# mdac-attenuator.net
KiCad netlist of a schematic drawn in EAGLE
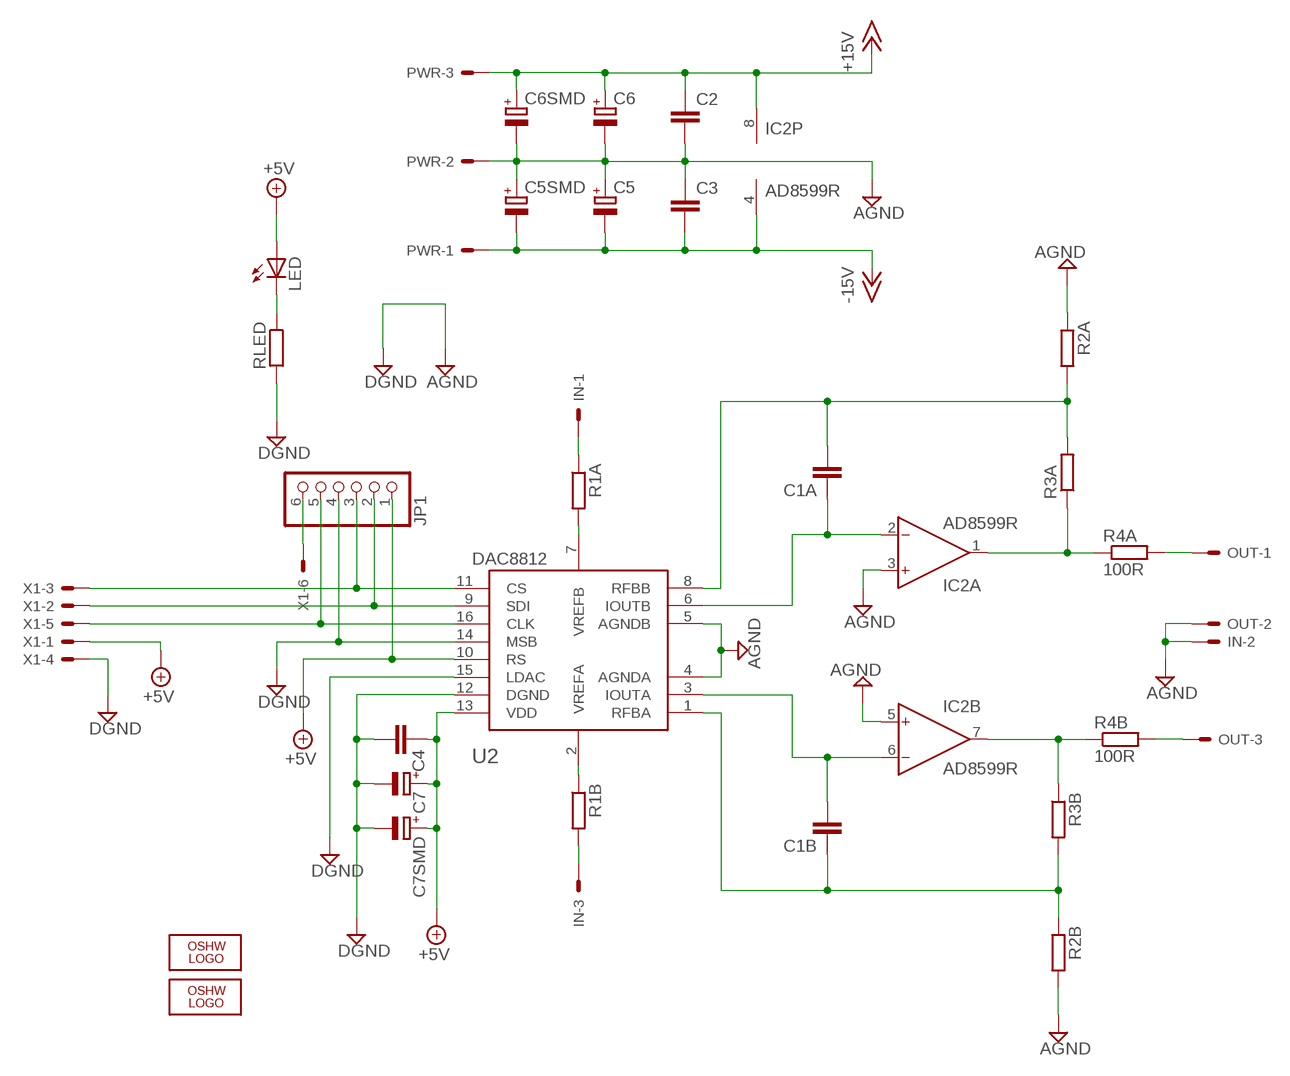
[diagram p0: schematic, sheet 1]

(export (version "E")
  (design (tool "Eeschema 10.0.6"))
  (components
    (comp (ref "C1A")
      (value "C-EUC0805")
      (footprint "eagle-import:C0805")
      (libsource (lib "eagle-import") (part "C-EUC0805"))
    )
    (comp (ref "C1B")
      (value "C-EUC0805")
      (footprint "eagle-import:C0805")
      (libsource (lib "eagle-import") (part "C-EUC0805"))
    )
    (comp (ref "C2")
      (value "C-EUC1206")
      (footprint "eagle-import:C1206")
      (libsource (lib "eagle-import") (part "C-EUC1206"))
    )
    (comp (ref "C3")
      (value "C-EUC1206")
      (footprint "eagle-import:C1206")
      (libsource (lib "eagle-import") (part "C-EUC1206"))
    )
    (comp (ref "C4")
      (value "C-EUC1206")
      (footprint "eagle-import:C1206")
      (libsource (lib "eagle-import") (part "C-EUC1206"))
    )
    (comp (ref "C5")
      (value "CPOL-EUE3.5-8")
      (footprint "eagle-import:E3,5-8")
      (libsource (lib "eagle-import") (part "CPOL-EUE3.5-8"))
    )
    (comp (ref "C5SMD")
      (value "CPOL-EUE")
      (footprint "eagle-import:PANASONIC_E")
      (libsource (lib "eagle-import") (part "CPOL-EUE"))
    )
    (comp (ref "C6")
      (value "CPOL-EUE3.5-8")
      (footprint "eagle-import:E3,5-8")
      (libsource (lib "eagle-import") (part "CPOL-EUE3.5-8"))
    )
    (comp (ref "C6SMD")
      (value "CPOL-EUE")
      (footprint "eagle-import:PANASONIC_E")
      (libsource (lib "eagle-import") (part "CPOL-EUE"))
    )
    (comp (ref "C7")
      (value "CPOL-EUE3.5-8")
      (footprint "eagle-import:E3,5-8")
      (libsource (lib "eagle-import") (part "CPOL-EUE3.5-8"))
    )
    (comp (ref "C7SMD")
      (value "CPOL-EUD")
      (footprint "eagle-import:PANASONIC_D")
      (libsource (lib "eagle-import") (part "CPOL-EUD"))
    )
    (comp (ref "IC2")
      (value "AD8599R")
      (footprint "eagle-import:SO8")
      (libsource (lib "eagle-import") (part "AD8599R"))
    )
    (comp (ref "IN")
      (value "22-23-2031")
      (footprint "eagle-import:22-23-2031")
      (fields (field (name "MF") "MOLEX"))
      (libsource (lib "eagle-import") (part "22-23-2031"))
    )
    (comp (ref "JP1")
      (value "PINHD-1X6")
      (footprint "eagle-import:1X06")
      (libsource (lib "eagle-import") (part "PINHD-1X6"))
    )
    (comp (ref "LED")
      (value "LEDSMT1206")
      (footprint "eagle-import:1206")
      (libsource (lib "eagle-import") (part "LEDSMT1206"))
    )
    (comp (ref "LOGO1")
      (value "OSHW_LOGO_FILLX0200-NT")
      (footprint "eagle-import:OSHW_FILLX200_NOTEXT")
      (libsource (lib "eagle-import") (part "OSHW_LOGO_FILLX0200-NT"))
    )
    (comp (ref "LOGO2")
      (value "OSHW_LOGO_FILLX0200-NT")
      (footprint "eagle-import:OSHW_FILLX200_NOTEXT")
      (libsource (lib "eagle-import") (part "OSHW_LOGO_FILLX0200-NT"))
    )
    (comp (ref "OUT")
      (value "22-23-2031")
      (footprint "eagle-import:22-23-2031")
      (fields (field (name "MF") "MOLEX"))
      (libsource (lib "eagle-import") (part "22-23-2031"))
    )
    (comp (ref "PWR")
      (value "22-23-2031")
      (footprint "eagle-import:22-23-2031")
      (fields (field (name "MF") "MOLEX"))
      (libsource (lib "eagle-import") (part "22-23-2031"))
    )
    (comp (ref "R1A")
      (value "R-EU_R1206")
      (footprint "eagle-import:R1206")
      (libsource (lib "eagle-import") (part "R-EU_R1206"))
    )
    (comp (ref "R1B")
      (value "R-EU_R1206")
      (footprint "eagle-import:R1206")
      (libsource (lib "eagle-import") (part "R-EU_R1206"))
    )
    (comp (ref "R2A")
      (value "R-EU_R1206")
      (footprint "eagle-import:R1206")
      (libsource (lib "eagle-import") (part "R-EU_R1206"))
    )
    (comp (ref "R2B")
      (value "R-EU_R1206")
      (footprint "eagle-import:R1206")
      (libsource (lib "eagle-import") (part "R-EU_R1206"))
    )
    (comp (ref "R3A")
      (value "R-EU_R1206")
      (footprint "eagle-import:R1206")
      (libsource (lib "eagle-import") (part "R-EU_R1206"))
    )
    (comp (ref "R3B")
      (value "R-EU_R1206")
      (footprint "eagle-import:R1206")
      (libsource (lib "eagle-import") (part "R-EU_R1206"))
    )
    (comp (ref "R4A")
      (value "100R")
      (footprint "eagle-import:R1206")
      (libsource (lib "eagle-import") (part "R-EU_R1206"))
    )
    (comp (ref "R4B")
      (value "100R")
      (footprint "eagle-import:R1206")
      (libsource (lib "eagle-import") (part "R-EU_R1206"))
    )
    (comp (ref "RLED")
      (value "R-EU_R1206")
      (footprint "eagle-import:R1206")
      (libsource (lib "eagle-import") (part "R-EU_R1206"))
    )
    (comp (ref "U2")
      (value "DAC8812")
      (footprint "eagle-import:TSSOP16")
      (libsource (lib "eagle-import") (part "DAC8812"))
    )
    (comp (ref "X1")
      (value "22-23-2061")
      (footprint "eagle-import:22-23-2061")
      (fields (field (name "MF") "MOLEX"))
      (libsource (lib "eagle-import") (part "22-23-2061"))
    )
  )
  (nets
    (net (code "1") (name "+5V") (class "Default")
      (node (ref "C4") (pin "1") (pinfunction "1_1") (pintype "passive"))
      (node (ref "C7") (pin "+") (pinfunction "+_+") (pintype "passive"))
      (node (ref "C7SMD") (pin "+") (pinfunction "+_+") (pintype "passive"))
      (node (ref "JP1") (pin "1") (pinfunction "1_1") (pintype "passive"))
      (node (ref "LED") (pin "A") (pinfunction "A_A") (pintype "passive"))
      (node (ref "U2") (pin "10") (pinfunction "RS_10") (pintype "input"))
      (node (ref "U2") (pin "13") (pinfunction "VDD_13") (pintype "power_in"))
      (node (ref "X1") (pin "1") (pinfunction "S_1") (pintype "passive"))
    )
    (net (code "2") (name "+15V") (class "Default")
      (node (ref "C2") (pin "1") (pinfunction "1_1") (pintype "passive"))
      (node (ref "C6") (pin "+") (pinfunction "+_+") (pintype "passive"))
      (node (ref "C6SMD") (pin "+") (pinfunction "+_+") (pintype "passive"))
      (node (ref "IC2") (pin "8") (pinfunction "V+_8") (pintype "power_in"))
      (node (ref "PWR") (pin "3") (pinfunction "S_3") (pintype "passive"))
    )
    (net (code "3") (name "-15V") (class "Default")
      (node (ref "C3") (pin "2") (pinfunction "2_2") (pintype "passive"))
      (node (ref "C5") (pin "-") (pinfunction "-_-") (pintype "passive"))
      (node (ref "C5SMD") (pin "-") (pinfunction "-_-") (pintype "passive"))
      (node (ref "IC2") (pin "4") (pinfunction "V-_4") (pintype "power_in"))
      (node (ref "PWR") (pin "1") (pinfunction "S_1") (pintype "passive"))
    )
    (net (code "4") (name "AGND") (class "Default")
      (node (ref "C2") (pin "2") (pinfunction "2_2") (pintype "passive"))
      (node (ref "C3") (pin "1") (pinfunction "1_1") (pintype "passive"))
      (node (ref "C4") (pin "2") (pinfunction "2_2") (pintype "passive"))
      (node (ref "C5") (pin "+") (pinfunction "+_+") (pintype "passive"))
      (node (ref "C5SMD") (pin "+") (pinfunction "+_+") (pintype "passive"))
      (node (ref "C6") (pin "-") (pinfunction "-_-") (pintype "passive"))
      (node (ref "C6SMD") (pin "-") (pinfunction "-_-") (pintype "passive"))
      (node (ref "C7") (pin "-") (pinfunction "-_-") (pintype "passive"))
      (node (ref "C7SMD") (pin "-") (pinfunction "-_-") (pintype "passive"))
      (node (ref "IC2") (pin "3") (pinfunction "IN+_3") (pintype "input"))
      (node (ref "IC2") (pin "5") (pinfunction "IN+_5") (pintype "input"))
      (node (ref "IN") (pin "2") (pinfunction "S_2") (pintype "passive"))
      (node (ref "JP1") (pin "4") (pinfunction "4_4") (pintype "passive"))
      (node (ref "OUT") (pin "2") (pinfunction "S_2") (pintype "passive"))
      (node (ref "PWR") (pin "2") (pinfunction "S_2") (pintype "passive"))
      (node (ref "R2A") (pin "1") (pinfunction "1_1") (pintype "passive"))
      (node (ref "R2B") (pin "2") (pinfunction "2_2") (pintype "passive"))
      (node (ref "RLED") (pin "2") (pinfunction "2_2") (pintype "passive"))
      (node (ref "U2") (pin "12") (pinfunction "DGND_12") (pintype "power_in"))
      (node (ref "U2") (pin "14") (pinfunction "MSB_14") (pintype "input"))
      (node (ref "U2") (pin "15") (pinfunction "LDAC_15") (pintype "input"))
      (node (ref "U2") (pin "4") (pinfunction "AGNDA_4") (pintype "output"))
      (node (ref "U2") (pin "5") (pinfunction "AGNDB_5") (pintype "output"))
      (node (ref "X1") (pin "4") (pinfunction "S_4") (pintype "passive"))
    )
    (net (code "5") (name "Net-(IC2A-IN-)") (class "Default")
      (node (ref "C1A") (pin "1") (pinfunction "1_1") (pintype "passive"))
      (node (ref "IC2") (pin "2") (pinfunction "IN-_2") (pintype "input"))
      (node (ref "U2") (pin "6") (pinfunction "IOUTB_6") (pintype "output"))
    )
    (net (code "6") (name "Net-(IC2A-OUT)") (class "Default")
      (node (ref "IC2") (pin "1") (pinfunction "OUT_1") (pintype "output"))
      (node (ref "R3A") (pin "1") (pinfunction "1_1") (pintype "passive"))
      (node (ref "R4A") (pin "1") (pinfunction "1_1") (pintype "passive"))
    )
    (net (code "7") (name "Net-(IC2B-IN-)") (class "Default")
      (node (ref "C1B") (pin "2") (pinfunction "2_2") (pintype "passive"))
      (node (ref "IC2") (pin "6") (pinfunction "IN-_6") (pintype "input"))
      (node (ref "U2") (pin "3") (pinfunction "IOUTA_3") (pintype "output"))
    )
    (net (code "8") (name "Net-(IC2B-OUT)") (class "Default")
      (node (ref "IC2") (pin "7") (pinfunction "OUT_7") (pintype "output"))
      (node (ref "R3B") (pin "1") (pinfunction "1_1") (pintype "passive"))
      (node (ref "R4B") (pin "1") (pinfunction "1_1") (pintype "passive"))
    )
    (net (code "9") (name "Net-(INA-S)") (class "Default")
      (node (ref "IN") (pin "1") (pinfunction "S_1") (pintype "passive"))
      (node (ref "R1A") (pin "1") (pinfunction "1_1") (pintype "passive"))
    )
    (net (code "10") (name "Net-(INC-S)") (class "Default")
      (node (ref "IN") (pin "3") (pinfunction "S_3") (pintype "passive"))
      (node (ref "R1B") (pin "2") (pinfunction "2_2") (pintype "passive"))
    )
    (net (code "11") (name "Net-(LED-PadC)") (class "Default")
      (node (ref "LED") (pin "C") (pinfunction "C_C") (pintype "passive"))
      (node (ref "RLED") (pin "1") (pinfunction "1_1") (pintype "passive"))
    )
    (net (code "12") (name "Net-(OUTA-S)") (class "Default")
      (node (ref "OUT") (pin "1") (pinfunction "S_1") (pintype "passive"))
      (node (ref "R4A") (pin "2") (pinfunction "2_2") (pintype "passive"))
    )
    (net (code "13") (name "Net-(OUTC-S)") (class "Default")
      (node (ref "OUT") (pin "3") (pinfunction "S_3") (pintype "passive"))
      (node (ref "R4B") (pin "2") (pinfunction "2_2") (pintype "passive"))
    )
    (net (code "14") (name "Net-(U2-CLK)") (class "Default")
      (node (ref "JP1") (pin "5") (pinfunction "5_5") (pintype "passive"))
      (node (ref "U2") (pin "16") (pinfunction "CLK_16") (pintype "input"))
      (node (ref "X1") (pin "5") (pinfunction "S_5") (pintype "passive"))
    )
    (net (code "15") (name "Net-(U2-CS)") (class "Default")
      (node (ref "JP1") (pin "3") (pinfunction "3_3") (pintype "passive"))
      (node (ref "U2") (pin "11") (pinfunction "CS_11") (pintype "input"))
      (node (ref "X1") (pin "3") (pinfunction "S_3") (pintype "passive"))
    )
    (net (code "16") (name "Net-(U2-RFBA)") (class "Default")
      (node (ref "C1B") (pin "1") (pinfunction "1_1") (pintype "passive"))
      (node (ref "R2B") (pin "1") (pinfunction "1_1") (pintype "passive"))
      (node (ref "R3B") (pin "2") (pinfunction "2_2") (pintype "passive"))
      (node (ref "U2") (pin "1") (pinfunction "RFBA_1") (pintype "bidirectional"))
    )
    (net (code "17") (name "Net-(U2-RFBB)") (class "Default")
      (node (ref "C1A") (pin "2") (pinfunction "2_2") (pintype "passive"))
      (node (ref "R2A") (pin "2") (pinfunction "2_2") (pintype "passive"))
      (node (ref "R3A") (pin "2") (pinfunction "2_2") (pintype "passive"))
      (node (ref "U2") (pin "8") (pinfunction "RFBB_8") (pintype "bidirectional"))
    )
    (net (code "18") (name "Net-(U2-SDI)") (class "Default")
      (node (ref "JP1") (pin "2") (pinfunction "2_2") (pintype "passive"))
      (node (ref "U2") (pin "9") (pinfunction "SDI_9") (pintype "input"))
      (node (ref "X1") (pin "2") (pinfunction "S_2") (pintype "passive"))
    )
    (net (code "19") (name "Net-(U2-VREFA)") (class "Default")
      (node (ref "R1B") (pin "1") (pinfunction "1_1") (pintype "passive"))
      (node (ref "U2") (pin "2") (pinfunction "VREFA_2") (pintype "input"))
    )
    (net (code "20") (name "Net-(U2-VREFB)") (class "Default")
      (node (ref "R1A") (pin "2") (pinfunction "2_2") (pintype "passive"))
      (node (ref "U2") (pin "7") (pinfunction "VREFB_7") (pintype "input"))
    )
    (net (code "21") (name "Net-(X1F-S)") (class "Default")
      (node (ref "JP1") (pin "6") (pinfunction "6_6") (pintype "passive"))
      (node (ref "X1") (pin "6") (pinfunction "S_6") (pintype "passive"))
    )
  )
)
